# carrierboard.net
KiCad netlist of a schematic drawn in EAGLE
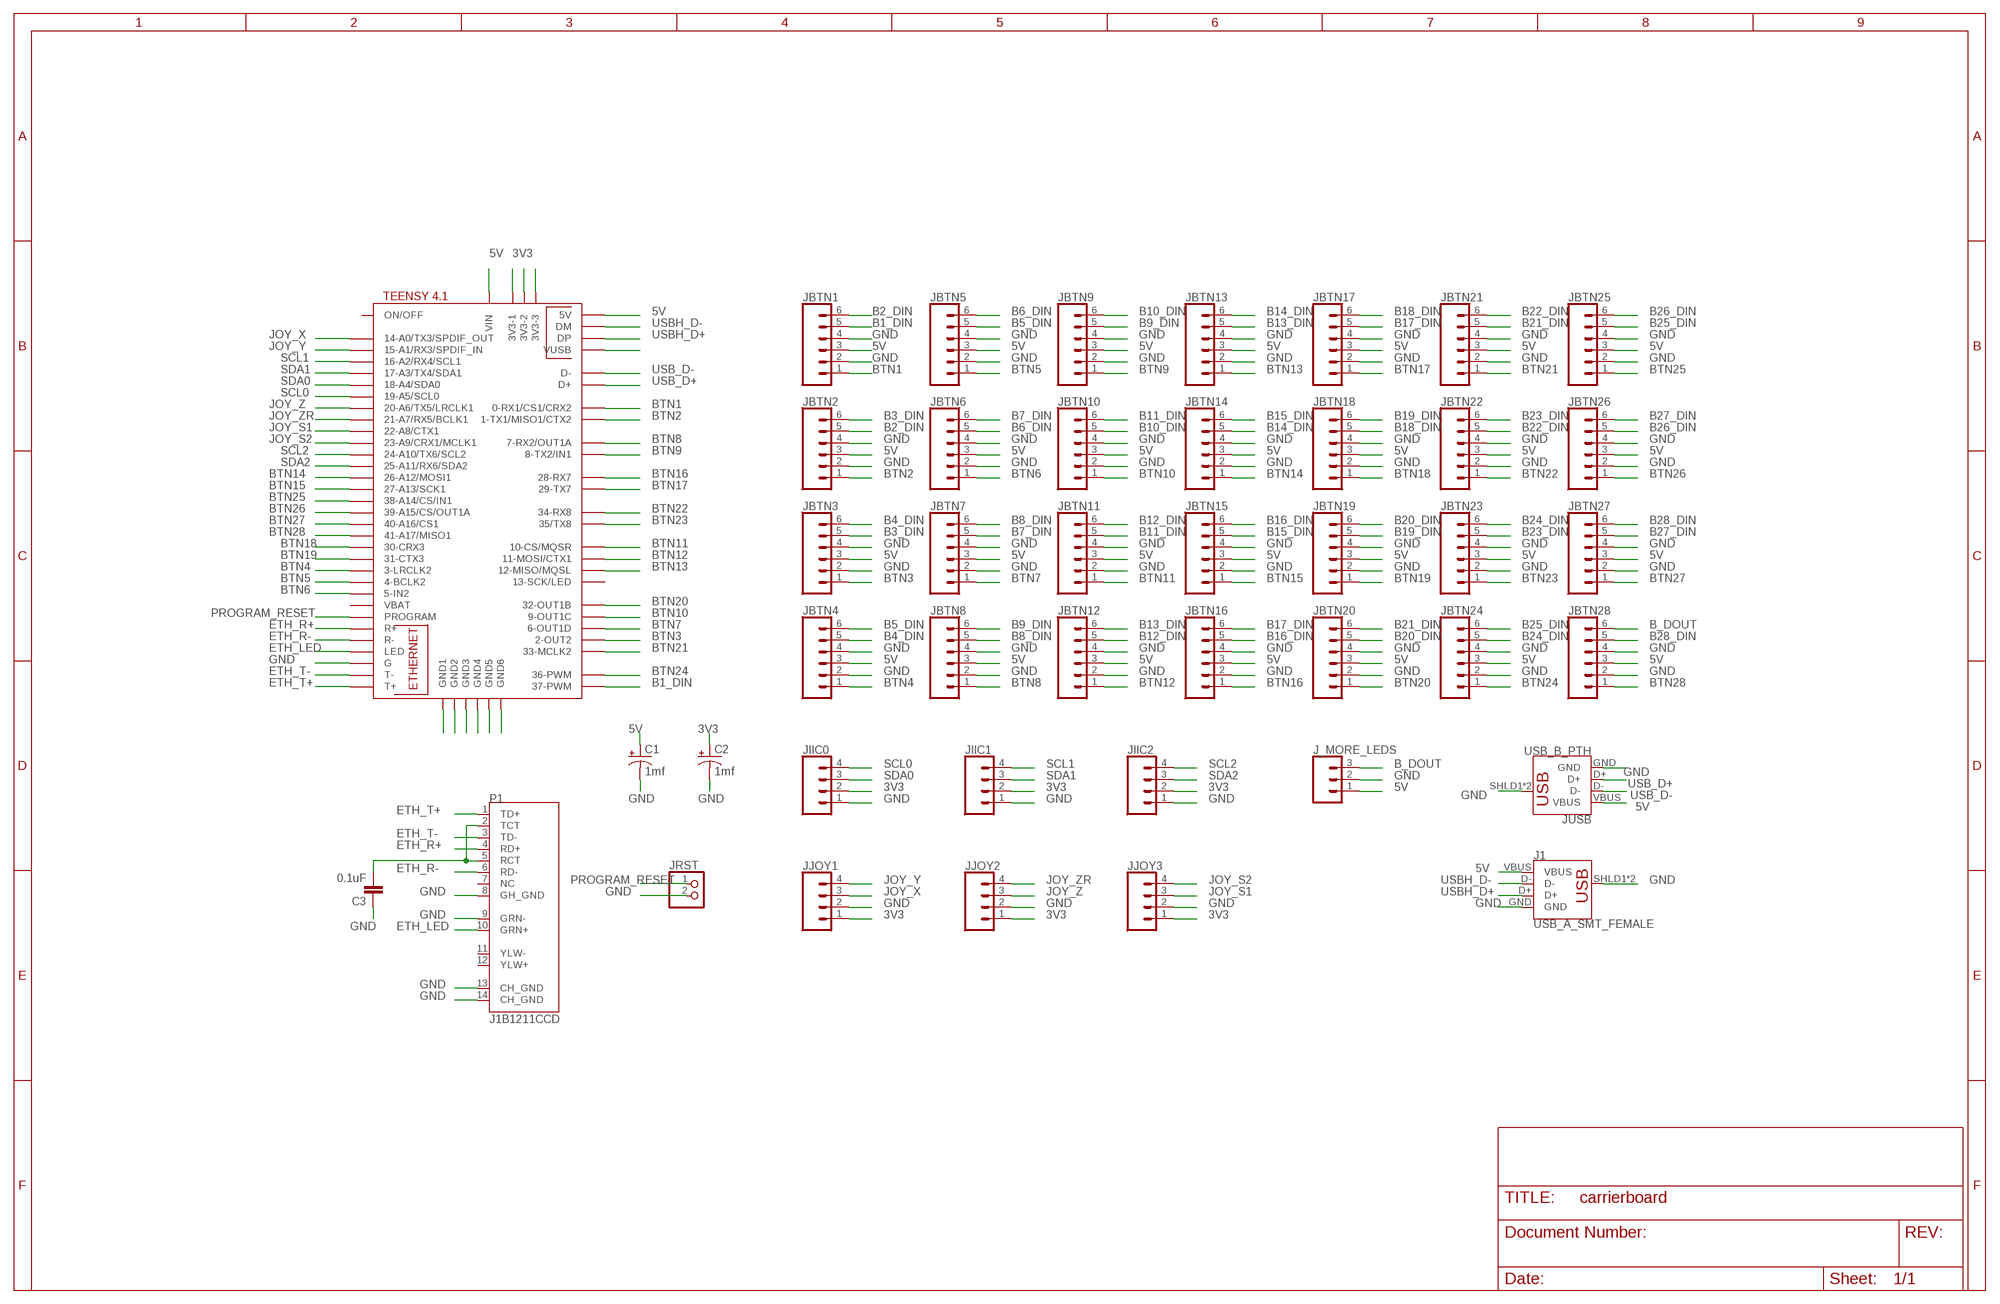
[diagram p0: schematic, sheet 1]

(export (version "E")
  (design (tool "Eeschema 10.0.6"))
  (components
    (comp (ref "C1")
      (value "1mf")
      (footprint "eagle-import:CPOL-RADIAL-5MM-10MM-KIT")
      (libsource (lib "eagle-import") (part "1000UF-RADIAL-5MM-35V-20%-KIT"))
    )
    (comp (ref "C2")
      (value "1mf")
      (footprint "eagle-import:CPOL-RADIAL-5MM-10MM-KIT")
      (libsource (lib "eagle-import") (part "1000UF-RADIAL-5MM-35V-20%-KIT"))
    )
    (comp (ref "C3")
      (value "0.1uF")
      (footprint "eagle-import:CAP-PTH-SMALL-KIT")
      (libsource (lib "eagle-import") (part "0.1UF-KIT-EZ-50V-20%"))
    )
    (comp (ref "J1")
      (value "USB_A_SMT_FEMALE")
      (footprint "eagle-import:USB-A-S-SILK-FEMALE")
      (libsource (lib "eagle-import") (part "USB_A_SMT_FEMALE"))
    )
    (comp (ref "JBTN1")
      (value "CONN_06SILK_FEMALE_PTH")
      (footprint "eagle-import:1X06")
      (libsource (lib "eagle-import") (part "CONN_06SILK_FEMALE_PTH"))
    )
    (comp (ref "JBTN2")
      (value "CONN_06SILK_FEMALE_PTH")
      (footprint "eagle-import:1X06")
      (libsource (lib "eagle-import") (part "CONN_06SILK_FEMALE_PTH"))
    )
    (comp (ref "JBTN3")
      (value "CONN_06SILK_FEMALE_PTH")
      (footprint "eagle-import:1X06")
      (libsource (lib "eagle-import") (part "CONN_06SILK_FEMALE_PTH"))
    )
    (comp (ref "JBTN4")
      (value "CONN_06SILK_FEMALE_PTH")
      (footprint "eagle-import:1X06")
      (libsource (lib "eagle-import") (part "CONN_06SILK_FEMALE_PTH"))
    )
    (comp (ref "JBTN5")
      (value "CONN_06SILK_FEMALE_PTH")
      (footprint "eagle-import:1X06")
      (libsource (lib "eagle-import") (part "CONN_06SILK_FEMALE_PTH"))
    )
    (comp (ref "JBTN6")
      (value "CONN_06SILK_FEMALE_PTH")
      (footprint "eagle-import:1X06")
      (libsource (lib "eagle-import") (part "CONN_06SILK_FEMALE_PTH"))
    )
    (comp (ref "JBTN7")
      (value "CONN_06SILK_FEMALE_PTH")
      (footprint "eagle-import:1X06")
      (libsource (lib "eagle-import") (part "CONN_06SILK_FEMALE_PTH"))
    )
    (comp (ref "JBTN8")
      (value "CONN_06SILK_FEMALE_PTH")
      (footprint "eagle-import:1X06")
      (libsource (lib "eagle-import") (part "CONN_06SILK_FEMALE_PTH"))
    )
    (comp (ref "JBTN9")
      (value "CONN_06SILK_FEMALE_PTH")
      (footprint "eagle-import:1X06")
      (libsource (lib "eagle-import") (part "CONN_06SILK_FEMALE_PTH"))
    )
    (comp (ref "JBTN10")
      (value "CONN_06SILK_FEMALE_PTH")
      (footprint "eagle-import:1X06")
      (libsource (lib "eagle-import") (part "CONN_06SILK_FEMALE_PTH"))
    )
    (comp (ref "JBTN11")
      (value "CONN_06SILK_FEMALE_PTH")
      (footprint "eagle-import:1X06")
      (libsource (lib "eagle-import") (part "CONN_06SILK_FEMALE_PTH"))
    )
    (comp (ref "JBTN12")
      (value "CONN_06SILK_FEMALE_PTH")
      (footprint "eagle-import:1X06")
      (libsource (lib "eagle-import") (part "CONN_06SILK_FEMALE_PTH"))
    )
    (comp (ref "JBTN13")
      (value "CONN_06SILK_FEMALE_PTH")
      (footprint "eagle-import:1X06")
      (libsource (lib "eagle-import") (part "CONN_06SILK_FEMALE_PTH"))
    )
    (comp (ref "JBTN14")
      (value "CONN_06SILK_FEMALE_PTH")
      (footprint "eagle-import:1X06")
      (libsource (lib "eagle-import") (part "CONN_06SILK_FEMALE_PTH"))
    )
    (comp (ref "JBTN15")
      (value "CONN_06SILK_FEMALE_PTH")
      (footprint "eagle-import:1X06")
      (libsource (lib "eagle-import") (part "CONN_06SILK_FEMALE_PTH"))
    )
    (comp (ref "JBTN16")
      (value "CONN_06SILK_FEMALE_PTH")
      (footprint "eagle-import:1X06")
      (libsource (lib "eagle-import") (part "CONN_06SILK_FEMALE_PTH"))
    )
    (comp (ref "JBTN17")
      (value "CONN_06SILK_FEMALE_PTH")
      (footprint "eagle-import:1X06")
      (libsource (lib "eagle-import") (part "CONN_06SILK_FEMALE_PTH"))
    )
    (comp (ref "JBTN18")
      (value "CONN_06SILK_FEMALE_PTH")
      (footprint "eagle-import:1X06")
      (libsource (lib "eagle-import") (part "CONN_06SILK_FEMALE_PTH"))
    )
    (comp (ref "JBTN19")
      (value "CONN_06SILK_FEMALE_PTH")
      (footprint "eagle-import:1X06")
      (libsource (lib "eagle-import") (part "CONN_06SILK_FEMALE_PTH"))
    )
    (comp (ref "JBTN20")
      (value "CONN_06SILK_FEMALE_PTH")
      (footprint "eagle-import:1X06")
      (libsource (lib "eagle-import") (part "CONN_06SILK_FEMALE_PTH"))
    )
    (comp (ref "JBTN21")
      (value "CONN_06SILK_FEMALE_PTH")
      (footprint "eagle-import:1X06")
      (libsource (lib "eagle-import") (part "CONN_06SILK_FEMALE_PTH"))
    )
    (comp (ref "JBTN22")
      (value "CONN_06SILK_FEMALE_PTH")
      (footprint "eagle-import:1X06")
      (libsource (lib "eagle-import") (part "CONN_06SILK_FEMALE_PTH"))
    )
    (comp (ref "JBTN23")
      (value "CONN_06SILK_FEMALE_PTH")
      (footprint "eagle-import:1X06")
      (libsource (lib "eagle-import") (part "CONN_06SILK_FEMALE_PTH"))
    )
    (comp (ref "JBTN24")
      (value "CONN_06SILK_FEMALE_PTH")
      (footprint "eagle-import:1X06")
      (libsource (lib "eagle-import") (part "CONN_06SILK_FEMALE_PTH"))
    )
    (comp (ref "JBTN25")
      (value "CONN_06SILK_FEMALE_PTH")
      (footprint "eagle-import:1X06")
      (libsource (lib "eagle-import") (part "CONN_06SILK_FEMALE_PTH"))
    )
    (comp (ref "JBTN26")
      (value "CONN_06SILK_FEMALE_PTH")
      (footprint "eagle-import:1X06")
      (libsource (lib "eagle-import") (part "CONN_06SILK_FEMALE_PTH"))
    )
    (comp (ref "JBTN27")
      (value "CONN_06SILK_FEMALE_PTH")
      (footprint "eagle-import:1X06")
      (libsource (lib "eagle-import") (part "CONN_06SILK_FEMALE_PTH"))
    )
    (comp (ref "JBTN28")
      (value "CONN_06SILK_FEMALE_PTH")
      (footprint "eagle-import:1X06")
      (libsource (lib "eagle-import") (part "CONN_06SILK_FEMALE_PTH"))
    )
    (comp (ref "JIIC0")
      (value "CONN_04POLAR")
      (footprint "eagle-import:MOLEX-1X4")
      (libsource (lib "eagle-import") (part "CONN_04POLAR"))
    )
    (comp (ref "JIIC1")
      (value "CONN_04POLAR")
      (footprint "eagle-import:MOLEX-1X4")
      (libsource (lib "eagle-import") (part "CONN_04POLAR"))
    )
    (comp (ref "JIIC2")
      (value "CONN_04POLAR")
      (footprint "eagle-import:MOLEX-1X4")
      (libsource (lib "eagle-import") (part "CONN_04POLAR"))
    )
    (comp (ref "JJOY1")
      (value "CONN_04LONGPADS")
      (footprint "eagle-import:1X04_LONGPADS")
      (libsource (lib "eagle-import") (part "CONN_04LONGPADS"))
    )
    (comp (ref "JJOY2")
      (value "CONN_04LONGPADS")
      (footprint "eagle-import:1X04_LONGPADS")
      (libsource (lib "eagle-import") (part "CONN_04LONGPADS"))
    )
    (comp (ref "JJOY3")
      (value "CONN_04LONGPADS")
      (footprint "eagle-import:1X04_LONGPADS")
      (libsource (lib "eagle-import") (part "CONN_04LONGPADS"))
    )
    (comp (ref "JRST")
      (value "PINHD-1X2")
      (footprint "eagle-import:1X02")
      (libsource (lib "eagle-import") (part "PINHD-1X2"))
    )
    (comp (ref "JUSB")
      (value "USB_B_PTH")
      (footprint "eagle-import:USB-B-PTH")
      (libsource (lib "eagle-import") (part "USB_B_PTH"))
    )
    (comp (ref "J_MORE_LEDS")
      (value "CONN_03LONGPADS")
      (footprint "eagle-import:1X03_LONGPADS")
      (libsource (lib "eagle-import") (part "CONN_03LONGPADS"))
    )
    (comp (ref "P1")
      (value "J1B1211CCD")
      (footprint "eagle-import:J1B1211CCD")
      (libsource (lib "eagle-import") (part "J1B1211CCD"))
    )
    (comp (ref "U$1")
      (value "TEENSY41")
      (footprint "eagle-import:TEENSY41")
      (libsource (lib "eagle-import") (part "TEENSY41"))
    )
  )
  (nets
    (net (code "1") (name "/3V3") (class "Default")
      (node (ref "C2") (pin "+") (pinfunction "+_+") (pintype "passive"))
      (node (ref "JIIC0") (pin "2") (pinfunction "2_2") (pintype "passive"))
      (node (ref "JIIC1") (pin "2") (pinfunction "2_2") (pintype "passive"))
      (node (ref "JIIC2") (pin "2") (pinfunction "2_2") (pintype "passive"))
      (node (ref "JJOY1") (pin "1") (pinfunction "1_1") (pintype "passive"))
      (node (ref "JJOY2") (pin "1") (pinfunction "1_1") (pintype "passive"))
      (node (ref "JJOY3") (pin "1") (pinfunction "1_1") (pintype "passive"))
      (node (ref "U$1") (pin "3V3-1") (pinfunction "3V3-1_3V3-1") (pintype "bidirectional"))
      (node (ref "U$1") (pin "3V3-2") (pinfunction "3V3-2_3V3-2") (pintype "bidirectional"))
      (node (ref "U$1") (pin "3V3-3") (pinfunction "3V3-3_3V3-3") (pintype "bidirectional"))
    )
    (net (code "2") (name "/5V") (class "Default")
      (node (ref "C1") (pin "+") (pinfunction "+_+") (pintype "passive"))
      (node (ref "J1") (pin "VBUS") (pinfunction "VBUS_VBUS") (pintype "power_in"))
      (node (ref "JBTN1") (pin "3") (pinfunction "3_3") (pintype "passive"))
      (node (ref "JBTN10") (pin "3") (pinfunction "3_3") (pintype "passive"))
      (node (ref "JBTN11") (pin "3") (pinfunction "3_3") (pintype "passive"))
      (node (ref "JBTN12") (pin "3") (pinfunction "3_3") (pintype "passive"))
      (node (ref "JBTN13") (pin "3") (pinfunction "3_3") (pintype "passive"))
      (node (ref "JBTN14") (pin "3") (pinfunction "3_3") (pintype "passive"))
      (node (ref "JBTN15") (pin "3") (pinfunction "3_3") (pintype "passive"))
      (node (ref "JBTN16") (pin "3") (pinfunction "3_3") (pintype "passive"))
      (node (ref "JBTN17") (pin "3") (pinfunction "3_3") (pintype "passive"))
      (node (ref "JBTN18") (pin "3") (pinfunction "3_3") (pintype "passive"))
      (node (ref "JBTN19") (pin "3") (pinfunction "3_3") (pintype "passive"))
      (node (ref "JBTN2") (pin "3") (pinfunction "3_3") (pintype "passive"))
      (node (ref "JBTN20") (pin "3") (pinfunction "3_3") (pintype "passive"))
      (node (ref "JBTN21") (pin "3") (pinfunction "3_3") (pintype "passive"))
      (node (ref "JBTN22") (pin "3") (pinfunction "3_3") (pintype "passive"))
      (node (ref "JBTN23") (pin "3") (pinfunction "3_3") (pintype "passive"))
      (node (ref "JBTN24") (pin "3") (pinfunction "3_3") (pintype "passive"))
      (node (ref "JBTN25") (pin "3") (pinfunction "3_3") (pintype "passive"))
      (node (ref "JBTN26") (pin "3") (pinfunction "3_3") (pintype "passive"))
      (node (ref "JBTN27") (pin "3") (pinfunction "3_3") (pintype "passive"))
      (node (ref "JBTN28") (pin "3") (pinfunction "3_3") (pintype "passive"))
      (node (ref "JBTN3") (pin "3") (pinfunction "3_3") (pintype "passive"))
      (node (ref "JBTN4") (pin "3") (pinfunction "3_3") (pintype "passive"))
      (node (ref "JBTN5") (pin "3") (pinfunction "3_3") (pintype "passive"))
      (node (ref "JBTN6") (pin "3") (pinfunction "3_3") (pintype "passive"))
      (node (ref "JBTN7") (pin "3") (pinfunction "3_3") (pintype "passive"))
      (node (ref "JBTN8") (pin "3") (pinfunction "3_3") (pintype "passive"))
      (node (ref "JBTN9") (pin "3") (pinfunction "3_3") (pintype "passive"))
      (node (ref "JUSB") (pin "VBUS") (pinfunction "VBUS_VBUS") (pintype "power_in"))
      (node (ref "J_MORE_LEDS") (pin "1") (pinfunction "1_1") (pintype "passive"))
      (node (ref "U$1") (pin "+5V") (pinfunction "5V_+5V") (pintype "bidirectional"))
      (node (ref "U$1") (pin "VIN") (pinfunction "VIN_VIN") (pintype "bidirectional"))
    )
    (net (code "3") (name "/B1_DIN") (class "Default")
      (node (ref "JBTN1") (pin "5") (pinfunction "5_5") (pintype "passive"))
      (node (ref "U$1") (pin "37-PWM") (pinfunction "37-PWM_37-PWM") (pintype "bidirectional"))
    )
    (net (code "4") (name "/B2_DIN") (class "Default")
      (node (ref "JBTN1") (pin "6") (pinfunction "6_6") (pintype "passive"))
      (node (ref "JBTN2") (pin "5") (pinfunction "5_5") (pintype "passive"))
    )
    (net (code "5") (name "/B3_DIN") (class "Default")
      (node (ref "JBTN2") (pin "6") (pinfunction "6_6") (pintype "passive"))
      (node (ref "JBTN3") (pin "5") (pinfunction "5_5") (pintype "passive"))
    )
    (net (code "6") (name "/B4_DIN") (class "Default")
      (node (ref "JBTN3") (pin "6") (pinfunction "6_6") (pintype "passive"))
      (node (ref "JBTN4") (pin "5") (pinfunction "5_5") (pintype "passive"))
    )
    (net (code "7") (name "/B5_DIN") (class "Default")
      (node (ref "JBTN4") (pin "6") (pinfunction "6_6") (pintype "passive"))
      (node (ref "JBTN5") (pin "5") (pinfunction "5_5") (pintype "passive"))
    )
    (net (code "8") (name "/B6_DIN") (class "Default")
      (node (ref "JBTN5") (pin "6") (pinfunction "6_6") (pintype "passive"))
      (node (ref "JBTN6") (pin "5") (pinfunction "5_5") (pintype "passive"))
    )
    (net (code "9") (name "/B7_DIN") (class "Default")
      (node (ref "JBTN6") (pin "6") (pinfunction "6_6") (pintype "passive"))
      (node (ref "JBTN7") (pin "5") (pinfunction "5_5") (pintype "passive"))
    )
    (net (code "10") (name "/B8_DIN") (class "Default")
      (node (ref "JBTN7") (pin "6") (pinfunction "6_6") (pintype "passive"))
      (node (ref "JBTN8") (pin "5") (pinfunction "5_5") (pintype "passive"))
    )
    (net (code "11") (name "/B9_DIN") (class "Default")
      (node (ref "JBTN8") (pin "6") (pinfunction "6_6") (pintype "passive"))
      (node (ref "JBTN9") (pin "5") (pinfunction "5_5") (pintype "passive"))
    )
    (net (code "12") (name "/B10_DIN") (class "Default")
      (node (ref "JBTN10") (pin "5") (pinfunction "5_5") (pintype "passive"))
      (node (ref "JBTN9") (pin "6") (pinfunction "6_6") (pintype "passive"))
    )
    (net (code "13") (name "/B11_DIN") (class "Default")
      (node (ref "JBTN10") (pin "6") (pinfunction "6_6") (pintype "passive"))
      (node (ref "JBTN11") (pin "5") (pinfunction "5_5") (pintype "passive"))
    )
    (net (code "14") (name "/B12_DIN") (class "Default")
      (node (ref "JBTN11") (pin "6") (pinfunction "6_6") (pintype "passive"))
      (node (ref "JBTN12") (pin "5") (pinfunction "5_5") (pintype "passive"))
    )
    (net (code "15") (name "/B13_DIN") (class "Default")
      (node (ref "JBTN12") (pin "6") (pinfunction "6_6") (pintype "passive"))
      (node (ref "JBTN13") (pin "5") (pinfunction "5_5") (pintype "passive"))
    )
    (net (code "16") (name "/B14_DIN") (class "Default")
      (node (ref "JBTN13") (pin "6") (pinfunction "6_6") (pintype "passive"))
      (node (ref "JBTN14") (pin "5") (pinfunction "5_5") (pintype "passive"))
    )
    (net (code "17") (name "/B15_DIN") (class "Default")
      (node (ref "JBTN14") (pin "6") (pinfunction "6_6") (pintype "passive"))
      (node (ref "JBTN15") (pin "5") (pinfunction "5_5") (pintype "passive"))
    )
    (net (code "18") (name "/B16_DIN") (class "Default")
      (node (ref "JBTN15") (pin "6") (pinfunction "6_6") (pintype "passive"))
      (node (ref "JBTN16") (pin "5") (pinfunction "5_5") (pintype "passive"))
    )
    (net (code "19") (name "/B17_DIN") (class "Default")
      (node (ref "JBTN16") (pin "6") (pinfunction "6_6") (pintype "passive"))
      (node (ref "JBTN17") (pin "5") (pinfunction "5_5") (pintype "passive"))
    )
    (net (code "20") (name "/B18_DIN") (class "Default")
      (node (ref "JBTN17") (pin "6") (pinfunction "6_6") (pintype "passive"))
      (node (ref "JBTN18") (pin "5") (pinfunction "5_5") (pintype "passive"))
    )
    (net (code "21") (name "/B19_DIN") (class "Default")
      (node (ref "JBTN18") (pin "6") (pinfunction "6_6") (pintype "passive"))
      (node (ref "JBTN19") (pin "5") (pinfunction "5_5") (pintype "passive"))
    )
    (net (code "22") (name "/B20_DIN") (class "Default")
      (node (ref "JBTN19") (pin "6") (pinfunction "6_6") (pintype "passive"))
      (node (ref "JBTN20") (pin "5") (pinfunction "5_5") (pintype "passive"))
    )
    (net (code "23") (name "/B21_DIN") (class "Default")
      (node (ref "JBTN20") (pin "6") (pinfunction "6_6") (pintype "passive"))
      (node (ref "JBTN21") (pin "5") (pinfunction "5_5") (pintype "passive"))
    )
    (net (code "24") (name "/B22_DIN") (class "Default")
      (node (ref "JBTN21") (pin "6") (pinfunction "6_6") (pintype "passive"))
      (node (ref "JBTN22") (pin "5") (pinfunction "5_5") (pintype "passive"))
    )
    (net (code "25") (name "/B23_DIN") (class "Default")
      (node (ref "JBTN22") (pin "6") (pinfunction "6_6") (pintype "passive"))
      (node (ref "JBTN23") (pin "5") (pinfunction "5_5") (pintype "passive"))
    )
    (net (code "26") (name "/B24_DIN") (class "Default")
      (node (ref "JBTN23") (pin "6") (pinfunction "6_6") (pintype "passive"))
      (node (ref "JBTN24") (pin "5") (pinfunction "5_5") (pintype "passive"))
    )
    (net (code "27") (name "/B25_DIN") (class "Default")
      (node (ref "JBTN24") (pin "6") (pinfunction "6_6") (pintype "passive"))
      (node (ref "JBTN25") (pin "5") (pinfunction "5_5") (pintype "passive"))
    )
    (net (code "28") (name "/B26_DIN") (class "Default")
      (node (ref "JBTN25") (pin "6") (pinfunction "6_6") (pintype "passive"))
      (node (ref "JBTN26") (pin "5") (pinfunction "5_5") (pintype "passive"))
    )
    (net (code "29") (name "/B27_DIN") (class "Default")
      (node (ref "JBTN26") (pin "6") (pinfunction "6_6") (pintype "passive"))
      (node (ref "JBTN27") (pin "5") (pinfunction "5_5") (pintype "passive"))
    )
    (net (code "30") (name "/B28_DIN") (class "Default")
      (node (ref "JBTN27") (pin "6") (pinfunction "6_6") (pintype "passive"))
      (node (ref "JBTN28") (pin "5") (pinfunction "5_5") (pintype "passive"))
    )
    (net (code "31") (name "/BTN1") (class "Default")
      (node (ref "JBTN1") (pin "1") (pinfunction "1_1") (pintype "passive"))
      (node (ref "U$1") (pin "0-RX1/CS1/CRX2") (pinfunction "0-RX1/CS1/CRX2_0-RX1/CS1/CRX2") (pintype "bidirectional"))
    )
    (net (code "32") (name "/BTN2") (class "Default")
      (node (ref "JBTN2") (pin "1") (pinfunction "1_1") (pintype "passive"))
      (node (ref "U$1") (pin "1-TX1/MISO1/CTX2") (pinfunction "1-TX1/MISO1/CTX2_1-TX1/MISO1/CTX2") (pintype "bidirectional"))
    )
    (net (code "33") (name "/BTN3") (class "Default")
      (node (ref "JBTN3") (pin "1") (pinfunction "1_1") (pintype "passive"))
      (node (ref "U$1") (pin "2-OUT2") (pinfunction "2-OUT2_2-OUT2") (pintype "bidirectional"))
    )
    (net (code "34") (name "/BTN4") (class "Default")
      (node (ref "JBTN4") (pin "1") (pinfunction "1_1") (pintype "passive"))
      (node (ref "U$1") (pin "3-LRCLK2") (pinfunction "3-LRCLK2_3-LRCLK2") (pintype "bidirectional"))
    )
    (net (code "35") (name "/BTN5") (class "Default")
      (node (ref "JBTN5") (pin "1") (pinfunction "1_1") (pintype "passive"))
      (node (ref "U$1") (pin "4-BCLK2") (pinfunction "4-BCLK2_4-BCLK2") (pintype "bidirectional"))
    )
    (net (code "36") (name "/BTN6") (class "Default")
      (node (ref "JBTN6") (pin "1") (pinfunction "1_1") (pintype "passive"))
      (node (ref "U$1") (pin "5-IN2") (pinfunction "5-IN2_5-IN2") (pintype "bidirectional"))
    )
    (net (code "37") (name "/BTN7") (class "Default")
      (node (ref "JBTN7") (pin "1") (pinfunction "1_1") (pintype "passive"))
      (node (ref "U$1") (pin "6-OUT1D") (pinfunction "6-OUT1D_6-OUT1D") (pintype "bidirectional"))
    )
    (net (code "38") (name "/BTN8") (class "Default")
      (node (ref "JBTN8") (pin "1") (pinfunction "1_1") (pintype "passive"))
      (node (ref "U$1") (pin "7-RX2/OUT1A") (pinfunction "7-RX2/OUT1A_7-RX2/OUT1A") (pintype "bidirectional"))
    )
    (net (code "39") (name "/BTN9") (class "Default")
      (node (ref "JBTN9") (pin "1") (pinfunction "1_1") (pintype "passive"))
      (node (ref "U$1") (pin "8-TX2/IN1") (pinfunction "8-TX2/IN1_8-TX2/IN1") (pintype "bidirectional"))
    )
    (net (code "40") (name "/BTN10") (class "Default")
      (node (ref "JBTN10") (pin "1") (pinfunction "1_1") (pintype "passive"))
      (node (ref "U$1") (pin "9-OUT1C") (pinfunction "9-OUT1C_9-OUT1C") (pintype "bidirectional"))
    )
    (net (code "41") (name "/BTN11") (class "Default")
      (node (ref "JBTN11") (pin "1") (pinfunction "1_1") (pintype "passive"))
      (node (ref "U$1") (pin "10-CS\\MQSR") (pinfunction "10-CS/MQSR_10-CS\\MQSR") (pintype "bidirectional"))
    )
    (net (code "42") (name "/BTN12") (class "Default")
      (node (ref "JBTN12") (pin "1") (pinfunction "1_1") (pintype "passive"))
      (node (ref "U$1") (pin "11-MOSI/CTX1") (pinfunction "11-MOSI/CTX1_11-MOSI/CTX1") (pintype "bidirectional"))
    )
    (net (code "43") (name "/BTN13") (class "Default")
      (node (ref "JBTN13") (pin "1") (pinfunction "1_1") (pintype "passive"))
      (node (ref "U$1") (pin "12-MISO/MQSL") (pinfunction "12-MISO/MQSL_12-MISO/MQSL") (pintype "bidirectional"))
    )
    (net (code "44") (name "/BTN14") (class "Default")
      (node (ref "JBTN14") (pin "1") (pinfunction "1_1") (pintype "passive"))
      (node (ref "U$1") (pin "26-A12/MOSI1") (pinfunction "26-A12/MOSI1_26-A12/MOSI1") (pintype "bidirectional"))
    )
    (net (code "45") (name "/BTN15") (class "Default")
      (node (ref "JBTN15") (pin "1") (pinfunction "1_1") (pintype "passive"))
      (node (ref "U$1") (pin "27-A13/SCK1") (pinfunction "27-A13/SCK1_27-A13/SCK1") (pintype "bidirectional"))
    )
    (net (code "46") (name "/BTN16") (class "Default")
      (node (ref "JBTN16") (pin "1") (pinfunction "1_1") (pintype "passive"))
      (node (ref "U$1") (pin "28-RX7") (pinfunction "28-RX7_28-RX7") (pintype "bidirectional"))
    )
    (net (code "47") (name "/BTN17") (class "Default")
      (node (ref "JBTN17") (pin "1") (pinfunction "1_1") (pintype "passive"))
      (node (ref "U$1") (pin "29-TX7") (pinfunction "29-TX7_29-TX7") (pintype "bidirectional"))
    )
    (net (code "48") (name "/BTN18") (class "Default")
      (node (ref "JBTN18") (pin "1") (pinfunction "1_1") (pintype "passive"))
      (node (ref "U$1") (pin "30-CRX3") (pinfunction "30-CRX3_30-CRX3") (pintype "bidirectional"))
    )
    (net (code "49") (name "/BTN19") (class "Default")
      (node (ref "JBTN19") (pin "1") (pinfunction "1_1") (pintype "passive"))
      (node (ref "U$1") (pin "31-CTX3") (pinfunction "31-CTX3_31-CTX3") (pintype "bidirectional"))
    )
    (net (code "50") (name "/BTN20") (class "Default")
      (node (ref "JBTN20") (pin "1") (pinfunction "1_1") (pintype "passive"))
      (node (ref "U$1") (pin "32-OUT1B") (pinfunction "32-OUT1B_32-OUT1B") (pintype "bidirectional"))
    )
    (net (code "51") (name "/BTN21") (class "Default")
      (node (ref "JBTN21") (pin "1") (pinfunction "1_1") (pintype "passive"))
      (node (ref "U$1") (pin "33-MCLK2") (pinfunction "33-MCLK2_33-MCLK2") (pintype "bidirectional"))
    )
    (net (code "52") (name "/BTN22") (class "Default")
      (node (ref "JBTN22") (pin "1") (pinfunction "1_1") (pintype "passive"))
      (node (ref "U$1") (pin "34-RX8") (pinfunction "34-RX8_34-RX8") (pintype "bidirectional"))
    )
    (net (code "53") (name "/BTN23") (class "Default")
      (node (ref "JBTN23") (pin "1") (pinfunction "1_1") (pintype "passive"))
      (node (ref "U$1") (pin "35-TX8") (pinfunction "35/TX8_35-TX8") (pintype "bidirectional"))
    )
    (net (code "54") (name "/BTN24") (class "Default")
      (node (ref "JBTN24") (pin "1") (pinfunction "1_1") (pintype "passive"))
      (node (ref "U$1") (pin "36-PWM") (pinfunction "36-PWM_36-PWM") (pintype "bidirectional"))
    )
    (net (code "55") (name "/BTN25") (class "Default")
      (node (ref "JBTN25") (pin "1") (pinfunction "1_1") (pintype "passive"))
      (node (ref "U$1") (pin "38-A14/CS/IN1") (pinfunction "38-A14/CS/IN1_38-A14/CS/IN1") (pintype "bidirectional"))
    )
    (net (code "56") (name "/BTN26") (class "Default")
      (node (ref "JBTN26") (pin "1") (pinfunction "1_1") (pintype "passive"))
      (node (ref "U$1") (pin "39-A15/CS/OUT1A") (pinfunction "39-A15/CS/OUT1A_39-A15/CS/OUT1A") (pintype "bidirectional"))
    )
    (net (code "57") (name "/BTN27") (class "Default")
      (node (ref "JBTN27") (pin "1") (pinfunction "1_1") (pintype "passive"))
      (node (ref "U$1") (pin "40-A16/CS1") (pinfunction "40-A16/CS1_40-A16/CS1") (pintype "bidirectional"))
    )
    (net (code "58") (name "/BTN28") (class "Default")
      (node (ref "JBTN28") (pin "1") (pinfunction "1_1") (pintype "passive"))
      (node (ref "U$1") (pin "41-A17/MISO1") (pinfunction "41-A17/MISO1_41-A17/MISO1") (pintype "bidirectional"))
    )
    (net (code "59") (name "/B_DOUT") (class "Default")
      (node (ref "JBTN28") (pin "6") (pinfunction "6_6") (pintype "passive"))
      (node (ref "J_MORE_LEDS") (pin "3") (pinfunction "3_3") (pintype "passive"))
    )
    (net (code "60") (name "/ETH_LED") (class "Default")
      (node (ref "P1") (pin "10") (pinfunction "GRN+_10") (pintype "passive"))
      (node (ref "U$1") (pin "LED") (pinfunction "LED_LED") (pintype "bidirectional"))
    )
    (net (code "61") (name "/ETH_R+") (class "Default")
      (node (ref "P1") (pin "4") (pinfunction "RD+_4") (pintype "passive"))
      (node (ref "U$1") (pin "R+") (pinfunction "R+_R+") (pintype "bidirectional"))
    )
    (net (code "62") (name "/ETH_R-") (class "Default")
      (node (ref "P1") (pin "6") (pinfunction "RD-_6") (pintype "passive"))
      (node (ref "U$1") (pin "R-") (pinfunction "R-_R-") (pintype "bidirectional"))
    )
    (net (code "63") (name "/ETH_T+") (class "Default")
      (node (ref "P1") (pin "1") (pinfunction "TD+_1") (pintype "passive"))
      (node (ref "U$1") (pin "T+") (pinfunction "T+_T+") (pintype "bidirectional"))
    )
    (net (code "64") (name "/ETH_T-") (class "Default")
      (node (ref "P1") (pin "3") (pinfunction "TD-_3") (pintype "passive"))
      (node (ref "U$1") (pin "T-") (pinfunction "T-_T-") (pintype "bidirectional"))
    )
    (net (code "65") (name "/GND") (class "Default")
      (node (ref "C1") (pin "-") (pinfunction "-_-") (pintype "passive"))
      (node (ref "C2") (pin "-") (pinfunction "-_-") (pintype "passive"))
      (node (ref "C3") (pin "1") (pinfunction "1_1") (pintype "passive"))
      (node (ref "J1") (pin "GND") (pinfunction "GND_GND") (pintype "power_in"))
      (node (ref "J1") (pin "SHLD1") (pinfunction "SHIELD_SHLD1") (pintype "bidirectional"))
      (node (ref "J1") (pin "SHLD2") (pinfunction "SHIELD_SHLD2") (pintype "bidirectional"))
      (node (ref "JBTN1") (pin "2") (pinfunction "2_2") (pintype "passive"))
      (node (ref "JBTN1") (pin "4") (pinfunction "4_4") (pintype "passive"))
      (node (ref "JBTN10") (pin "2") (pinfunction "2_2") (pintype "passive"))
      (node (ref "JBTN10") (pin "4") (pinfunction "4_4") (pintype "passive"))
      (node (ref "JBTN11") (pin "2") (pinfunction "2_2") (pintype "passive"))
      (node (ref "JBTN11") (pin "4") (pinfunction "4_4") (pintype "passive"))
      (node (ref "JBTN12") (pin "2") (pinfunction "2_2") (pintype "passive"))
      (node (ref "JBTN12") (pin "4") (pinfunction "4_4") (pintype "passive"))
      (node (ref "JBTN13") (pin "2") (pinfunction "2_2") (pintype "passive"))
      (node (ref "JBTN13") (pin "4") (pinfunction "4_4") (pintype "passive"))
      (node (ref "JBTN14") (pin "2") (pinfunction "2_2") (pintype "passive"))
      (node (ref "JBTN14") (pin "4") (pinfunction "4_4") (pintype "passive"))
      (node (ref "JBTN15") (pin "2") (pinfunction "2_2") (pintype "passive"))
      (node (ref "JBTN15") (pin "4") (pinfunction "4_4") (pintype "passive"))
      (node (ref "JBTN16") (pin "2") (pinfunction "2_2") (pintype "passive"))
      (node (ref "JBTN16") (pin "4") (pinfunction "4_4") (pintype "passive"))
      (node (ref "JBTN17") (pin "2") (pinfunction "2_2") (pintype "passive"))
      (node (ref "JBTN17") (pin "4") (pinfunction "4_4") (pintype "passive"))
      (node (ref "JBTN18") (pin "2") (pinfunction "2_2") (pintype "passive"))
      (node (ref "JBTN18") (pin "4") (pinfunction "4_4") (pintype "passive"))
      (node (ref "JBTN19") (pin "2") (pinfunction "2_2") (pintype "passive"))
      (node (ref "JBTN19") (pin "4") (pinfunction "4_4") (pintype "passive"))
      (node (ref "JBTN2") (pin "2") (pinfunction "2_2") (pintype "passive"))
      (node (ref "JBTN2") (pin "4") (pinfunction "4_4") (pintype "passive"))
      (node (ref "JBTN20") (pin "2") (pinfunction "2_2") (pintype "passive"))
      (node (ref "JBTN20") (pin "4") (pinfunction "4_4") (pintype "passive"))
      (node (ref "JBTN21") (pin "2") (pinfunction "2_2") (pintype "passive"))
      (node (ref "JBTN21") (pin "4") (pinfunction "4_4") (pintype "passive"))
      (node (ref "JBTN22") (pin "2") (pinfunction "2_2") (pintype "passive"))
      (node (ref "JBTN22") (pin "4") (pinfunction "4_4") (pintype "passive"))
      (node (ref "JBTN23") (pin "2") (pinfunction "2_2") (pintype "passive"))
      (node (ref "JBTN23") (pin "4") (pinfunction "4_4") (pintype "passive"))
      (node (ref "JBTN24") (pin "2") (pinfunction "2_2") (pintype "passive"))
      (node (ref "JBTN24") (pin "4") (pinfunction "4_4") (pintype "passive"))
      (node (ref "JBTN25") (pin "2") (pinfunction "2_2") (pintype "passive"))
      (node (ref "JBTN25") (pin "4") (pinfunction "4_4") (pintype "passive"))
      (node (ref "JBTN26") (pin "2") (pinfunction "2_2") (pintype "passive"))
      (node (ref "JBTN26") (pin "4") (pinfunction "4_4") (pintype "passive"))
      (node (ref "JBTN27") (pin "2") (pinfunction "2_2") (pintype "passive"))
      (node (ref "JBTN27") (pin "4") (pinfunction "4_4") (pintype "passive"))
      (node (ref "JBTN28") (pin "2") (pinfunction "2_2") (pintype "passive"))
      (node (ref "JBTN28") (pin "4") (pinfunction "4_4") (pintype "passive"))
      (node (ref "JBTN3") (pin "2") (pinfunction "2_2") (pintype "passive"))
      (node (ref "JBTN3") (pin "4") (pinfunction "4_4") (pintype "passive"))
      (node (ref "JBTN4") (pin "2") (pinfunction "2_2") (pintype "passive"))
      (node (ref "JBTN4") (pin "4") (pinfunction "4_4") (pintype "passive"))
      (node (ref "JBTN5") (pin "2") (pinfunction "2_2") (pintype "passive"))
      (node (ref "JBTN5") (pin "4") (pinfunction "4_4") (pintype "passive"))
      (node (ref "JBTN6") (pin "2") (pinfunction "2_2") (pintype "passive"))
      (node (ref "JBTN6") (pin "4") (pinfunction "4_4") (pintype "passive"))
      (node (ref "JBTN7") (pin "2") (pinfunction "2_2") (pintype "passive"))
      (node (ref "JBTN7") (pin "4") (pinfunction "4_4") (pintype "passive"))
      (node (ref "JBTN8") (pin "2") (pinfunction "2_2") (pintype "passive"))
      (node (ref "JBTN8") (pin "4") (pinfunction "4_4") (pintype "passive"))
      (node (ref "JBTN9") (pin "2") (pinfunction "2_2") (pintype "passive"))
      (node (ref "JBTN9") (pin "4") (pinfunction "4_4") (pintype "passive"))
      (node (ref "JIIC0") (pin "1") (pinfunction "1_1") (pintype "passive"))
      (node (ref "JIIC1") (pin "1") (pinfunction "1_1") (pintype "passive"))
      (node (ref "JIIC2") (pin "1") (pinfunction "1_1") (pintype "passive"))
      (node (ref "JJOY1") (pin "2") (pinfunction "2_2") (pintype "passive"))
      (node (ref "JJOY2") (pin "2") (pinfunction "2_2") (pintype "passive"))
      (node (ref "JJOY3") (pin "2") (pinfunction "2_2") (pintype "passive"))
      (node (ref "JRST") (pin "2") (pinfunction "2_2") (pintype "passive"))
      (node (ref "JUSB") (pin "GND") (pinfunction "GND_GND") (pintype "power_in"))
      (node (ref "JUSB") (pin "SHLD1") (pinfunction "SHIELD_SHLD1") (pintype "bidirectional"))
      (node (ref "JUSB") (pin "SHLD2") (pinfunction "SHIELD_SHLD2") (pintype "bidirectional"))
      (node (ref "J_MORE_LEDS") (pin "2") (pinfunction "2_2") (pintype "passive"))
      (node (ref "P1") (pin "13") (pinfunction "CH_GND_13") (pintype "passive"))
      (node (ref "P1") (pin "14") (pinfunction "CH_GND_14") (pintype "passive"))
      (node (ref "P1") (pin "8") (pinfunction "GH_GND_8") (pintype "passive"))
      (node (ref "P1") (pin "9") (pinfunction "GRN-_9") (pintype "passive"))
      (node (ref "U$1") (pin "G") (pinfunction "G_G") (pintype "bidirectional"))
      (node (ref "U$1") (pin "GND1") (pinfunction "GND1_GND1") (pintype "bidirectional"))
      (node (ref "U$1") (pin "GND2") (pinfunction "GND2_GND2") (pintype "bidirectional"))
      (node (ref "U$1") (pin "GND3") (pinfunction "GND3_GND3") (pintype "bidirectional"))
      (node (ref "U$1") (pin "GND4") (pinfunction "GND4_GND4") (pintype "bidirectional"))
      (node (ref "U$1") (pin "GND5") (pinfunction "GND5_GND5") (pintype "bidirectional"))
      (node (ref "U$1") (pin "GND6") (pinfunction "GND6_GND6") (pintype "bidirectional"))
    )
    (net (code "66") (name "/JOY_S1") (class "Default")
      (node (ref "JJOY3") (pin "3") (pinfunction "3_3") (pintype "passive"))
      (node (ref "U$1") (pin "22-A8/CTX1") (pinfunction "22-A8/CTX1_22-A8/CTX1") (pintype "bidirectional"))
    )
    (net (code "67") (name "/JOY_S2") (class "Default")
      (node (ref "JJOY3") (pin "4") (pinfunction "4_4") (pintype "passive"))
      (node (ref "U$1") (pin "23-A9/CRX1/MCLK1") (pinfunction "23-A9/CRX1/MCLK1_23-A9/CRX1/MCLK1") (pintype "bidirectional"))
    )
    (net (code "68") (name "/JOY_X") (class "Default")
      (node (ref "JJOY1") (pin "3") (pinfunction "3_3") (pintype "passive"))
      (node (ref "U$1") (pin "14-A0/TX3/SPDIF_OUT") (pinfunction "14-A0/TX3/SPDIF_OUT_14-A0/TX3/SPDIF_OUT") (pintype "bidirectional"))
    )
    (net (code "69") (name "/JOY_Y") (class "Default")
      (node (ref "JJOY1") (pin "4") (pinfunction "4_4") (pintype "passive"))
      (node (ref "U$1") (pin "15-A1/RX3/SPDIF_IN") (pinfunction "15-A1/RX3/SPDIF_IN_15-A1/RX3/SPDIF_IN") (pintype "bidirectional"))
    )
    (net (code "70") (name "/JOY_Z") (class "Default")
      (node (ref "JJOY2") (pin "3") (pinfunction "3_3") (pintype "passive"))
      (node (ref "U$1") (pin "20-A6/TX5/LRCLK1") (pinfunction "20-A6/TX5/LRCLK1_20-A6/TX5/LRCLK1") (pintype "bidirectional"))
    )
    (net (code "71") (name "/JOY_ZR") (class "Default")
      (node (ref "JJOY2") (pin "4") (pinfunction "4_4") (pintype "passive"))
      (node (ref "U$1") (pin "21-A7/RX5/BCLK1") (pinfunction "21-A7/RX5/BCLK1_21-A7/RX5/BCLK1") (pintype "bidirectional"))
    )
    (net (code "72") (name "/PROGRAM_RESET") (class "Default")
      (node (ref "JRST") (pin "1") (pinfunction "1_1") (pintype "passive"))
      (node (ref "U$1") (pin "PROGRAM") (pinfunction "PROGRAM_PROGRAM") (pintype "bidirectional"))
    )
    (net (code "73") (name "/SCL0") (class "Default")
      (node (ref "JIIC0") (pin "4") (pinfunction "4_4") (pintype "passive"))
      (node (ref "U$1") (pin "19-A5/SCL0") (pinfunction "19-A5/SCL0_19-A5/SCL0") (pintype "bidirectional"))
    )
    (net (code "74") (name "/SCL1") (class "Default")
      (node (ref "JIIC1") (pin "4") (pinfunction "4_4") (pintype "passive"))
      (node (ref "U$1") (pin "16-A2/RX4/SCL1") (pinfunction "16-A2/RX4/SCL1_16-A2/RX4/SCL1") (pintype "bidirectional"))
    )
    (net (code "75") (name "/SCL2") (class "Default")
      (node (ref "JIIC2") (pin "4") (pinfunction "4_4") (pintype "passive"))
      (node (ref "U$1") (pin "24-A10/TX6/SCL2") (pinfunction "24-A10/TX6/SCL2_24-A10/TX6/SCL2") (pintype "bidirectional"))
    )
    (net (code "76") (name "/SDA0") (class "Default")
      (node (ref "JIIC0") (pin "3") (pinfunction "3_3") (pintype "passive"))
      (node (ref "U$1") (pin "18-A4/SDA0") (pinfunction "18-A4/SDA0_18-A4/SDA0") (pintype "bidirectional"))
    )
    (net (code "77") (name "/SDA1") (class "Default")
      (node (ref "JIIC1") (pin "3") (pinfunction "3_3") (pintype "passive"))
      (node (ref "U$1") (pin "17-A3/TX4/SDA1") (pinfunction "17-A3/TX4/SDA1_17-A3/TX4/SDA1") (pintype "bidirectional"))
    )
    (net (code "78") (name "/SDA2") (class "Default")
      (node (ref "JIIC2") (pin "3") (pinfunction "3_3") (pintype "passive"))
      (node (ref "U$1") (pin "25-A11/RX6/SDA2") (pinfunction "25-A11/RX6/SDA2_25-A11/RX6/SDA2") (pintype "bidirectional"))
    )
    (net (code "79") (name "/USBH_D+") (class "Default")
      (node (ref "J1") (pin "D+") (pinfunction "D+_D+") (pintype "bidirectional"))
      (node (ref "U$1") (pin "DP") (pinfunction "DP_DP") (pintype "bidirectional"))
    )
    (net (code "80") (name "/USBH_D-") (class "Default")
      (node (ref "J1") (pin "D-") (pinfunction "D-_D-") (pintype "bidirectional"))
      (node (ref "U$1") (pin "DM") (pinfunction "DM_DM") (pintype "bidirectional"))
    )
    (net (code "81") (name "/USB_D+") (class "Default")
      (node (ref "JUSB") (pin "D+") (pinfunction "D+_D+") (pintype "bidirectional"))
      (node (ref "U$1") (pin "D+") (pinfunction "D+_D+") (pintype "bidirectional"))
    )
    (net (code "82") (name "/USB_D-") (class "Default")
      (node (ref "JUSB") (pin "D-") (pinfunction "D-_D-") (pintype "bidirectional"))
      (node (ref "U$1") (pin "D-") (pinfunction "D-_D-") (pintype "bidirectional"))
    )
    (net (code "83") (name "Net-(P1-RCT)") (class "Default")
      (node (ref "C3") (pin "2") (pinfunction "2_2") (pintype "passive"))
      (node (ref "P1") (pin "2") (pinfunction "TCT_2") (pintype "passive"))
      (node (ref "P1") (pin "5") (pinfunction "RCT_5") (pintype "passive"))
    )
    (net (code "84") (name "unconnected-(P1-NC-Pad7)") (class "Default")
      (node (ref "P1") (pin "7") (pinfunction "NC_7") (pintype "passive"))
    )
    (net (code "85") (name "unconnected-(P1-YLW+-Pad12)") (class "Default")
      (node (ref "P1") (pin "12") (pinfunction "YLW+_12") (pintype "passive"))
    )
    (net (code "86") (name "unconnected-(P1-YLW--Pad11)") (class "Default")
      (node (ref "P1") (pin "11") (pinfunction "YLW-_11") (pintype "passive"))
    )
    (net (code "87") (name "unconnected-(U$1-Pad13-SCK{slash}LED)") (class "Default")
      (node (ref "U$1") (pin "13-SCK/LED") (pinfunction "13-SCK/LED_13-SCK/LED") (pintype "bidirectional"))
    )
    (net (code "88") (name "unconnected-(U$1-PadON{slash}OFF)") (class "Default")
      (node (ref "U$1") (pin "ON/OFF") (pinfunction "ON/OFF_ON/OFF") (pintype "bidirectional"))
    )
    (net (code "89") (name "unconnected-(U$1-PadVBAT)") (class "Default")
      (node (ref "U$1") (pin "VBAT") (pinfunction "VBAT_VBAT") (pintype "bidirectional"))
    )
    (net (code "90") (name "unconnected-(U$1-PadVUSB)") (class "Default")
      (node (ref "U$1") (pin "VUSB") (pinfunction "VUSB_VUSB") (pintype "bidirectional"))
    )
  )
)
